# rwqs.net
KiCad netlist of a schematic drawn in EAGLE
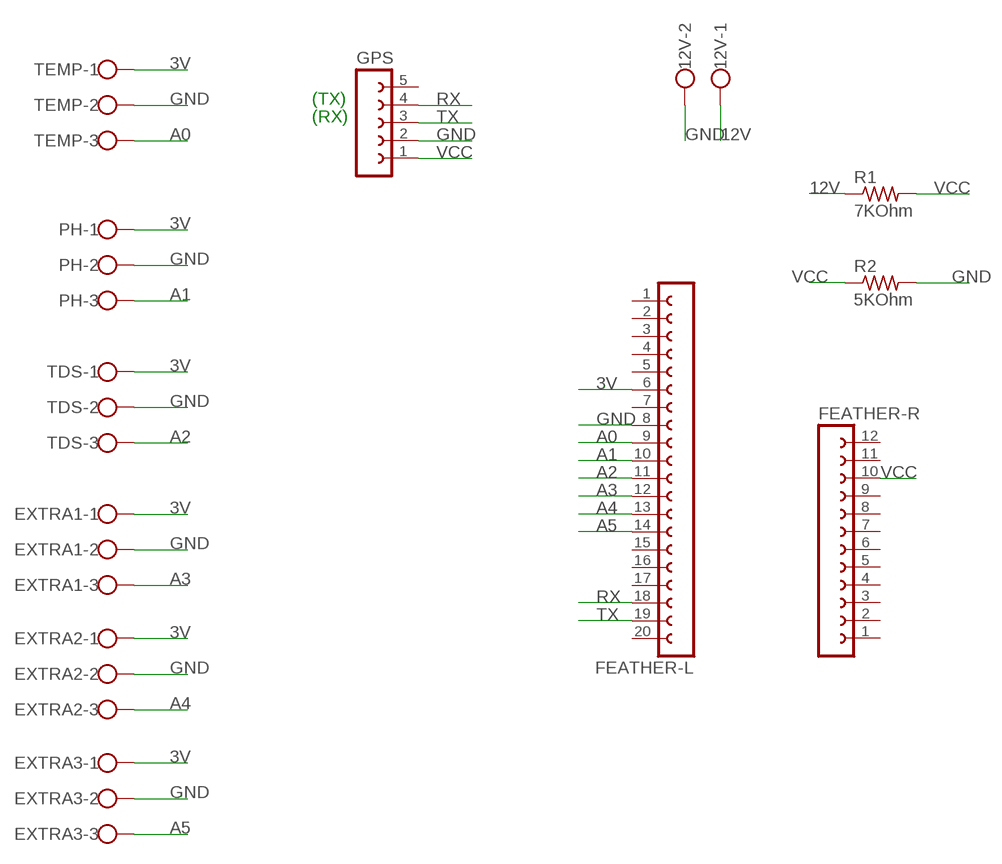
[diagram p0: schematic, sheet 1]

(export (version "E")
  (design (tool "Eeschema 10.0.6"))
  (components
    (comp (ref "12V")
      (value "W237-113")
      (footprint "eagle-import:W237-113")
      (libsource (lib "eagle-import") (part "W237-113"))
    )
    (comp (ref "EXTRA1")
      (value "W237-103")
      (footprint "eagle-import:W237-103")
      (fields (field (name "MPN") "237-103"))
      (libsource (lib "eagle-import") (part "W237-103"))
    )
    (comp (ref "EXTRA2")
      (value "W237-103")
      (footprint "eagle-import:W237-103")
      (fields (field (name "MPN") "237-103"))
      (libsource (lib "eagle-import") (part "W237-103"))
    )
    (comp (ref "EXTRA3")
      (value "W237-103")
      (footprint "eagle-import:W237-103")
      (fields (field (name "MPN") "237-103"))
      (libsource (lib "eagle-import") (part "W237-103"))
    )
    (comp (ref "FEATHER-L")
      (value "FE20-1")
      (footprint "eagle-import:FE20")
      (libsource (lib "eagle-import") (part "FE20-1"))
    )
    (comp (ref "FEATHER-R")
      (value "FE12-1")
      (footprint "eagle-import:FE12")
      (libsource (lib "eagle-import") (part "FE12-1"))
    )
    (comp (ref "GPS")
      (value "FE05-1")
      (footprint "eagle-import:FE05-1")
      (libsource (lib "eagle-import") (part "FE05-1"))
    )
    (comp (ref "PH")
      (value "W237-103")
      (footprint "eagle-import:W237-103")
      (fields (field (name "MPN") "237-103"))
      (libsource (lib "eagle-import") (part "W237-103"))
    )
    (comp (ref "R1")
      (value "7KOhm")
      (footprint "eagle-import:0204V")
      (libsource (lib "eagle-import") (part "R-US_0204/2V"))
    )
    (comp (ref "R2")
      (value "5KOhm")
      (footprint "eagle-import:0204V")
      (libsource (lib "eagle-import") (part "R-US_0204/2V"))
    )
    (comp (ref "TDS")
      (value "W237-103")
      (footprint "eagle-import:W237-103")
      (fields (field (name "MPN") "237-103"))
      (libsource (lib "eagle-import") (part "W237-103"))
    )
    (comp (ref "TEMP")
      (value "W237-103")
      (footprint "eagle-import:W237-103")
      (fields (field (name "MPN") "237-103"))
      (libsource (lib "eagle-import") (part "W237-103"))
    )
  )
  (nets
    (net (code "1") (name "/3V") (class "Default")
      (node (ref "EXTRA1") (pin "1") (pinfunction "KL_1") (pintype "passive"))
      (node (ref "EXTRA2") (pin "1") (pinfunction "KL_1") (pintype "passive"))
      (node (ref "EXTRA3") (pin "1") (pinfunction "KL_1") (pintype "passive"))
      (node (ref "FEATHER-L") (pin "6") (pinfunction "6_6") (pintype "passive"))
      (node (ref "PH") (pin "1") (pinfunction "KL_1") (pintype "passive"))
      (node (ref "TDS") (pin "1") (pinfunction "KL_1") (pintype "passive"))
      (node (ref "TEMP") (pin "1") (pinfunction "KL_1") (pintype "passive"))
    )
    (net (code "2") (name "/12V") (class "Default")
      (node (ref "12V") (pin "1") (pinfunction "KL_1") (pintype "passive"))
      (node (ref "R1") (pin "1") (pinfunction "1_1") (pintype "passive"))
    )
    (net (code "3") (name "/A0") (class "Default")
      (node (ref "FEATHER-L") (pin "9") (pinfunction "9_9") (pintype "passive"))
      (node (ref "TEMP") (pin "3") (pinfunction "KL_3") (pintype "passive"))
    )
    (net (code "4") (name "/A1") (class "Default")
      (node (ref "FEATHER-L") (pin "10") (pinfunction "10_10") (pintype "passive"))
      (node (ref "PH") (pin "3") (pinfunction "KL_3") (pintype "passive"))
    )
    (net (code "5") (name "/A2") (class "Default")
      (node (ref "FEATHER-L") (pin "11") (pinfunction "11_11") (pintype "passive"))
      (node (ref "TDS") (pin "3") (pinfunction "KL_3") (pintype "passive"))
    )
    (net (code "6") (name "/A3") (class "Default")
      (node (ref "EXTRA1") (pin "3") (pinfunction "KL_3") (pintype "passive"))
      (node (ref "FEATHER-L") (pin "12") (pinfunction "12_12") (pintype "passive"))
    )
    (net (code "7") (name "/A4") (class "Default")
      (node (ref "EXTRA2") (pin "3") (pinfunction "KL_3") (pintype "passive"))
      (node (ref "FEATHER-L") (pin "13") (pinfunction "13_13") (pintype "passive"))
    )
    (net (code "8") (name "/A5") (class "Default")
      (node (ref "EXTRA3") (pin "3") (pinfunction "KL_3") (pintype "passive"))
      (node (ref "FEATHER-L") (pin "14") (pinfunction "14_14") (pintype "passive"))
    )
    (net (code "9") (name "/GND") (class "Default")
      (node (ref "12V") (pin "2") (pinfunction "KL_2") (pintype "passive"))
      (node (ref "EXTRA1") (pin "2") (pinfunction "KL_2") (pintype "passive"))
      (node (ref "EXTRA2") (pin "2") (pinfunction "KL_2") (pintype "passive"))
      (node (ref "EXTRA3") (pin "2") (pinfunction "KL_2") (pintype "passive"))
      (node (ref "FEATHER-L") (pin "8") (pinfunction "8_8") (pintype "passive"))
      (node (ref "GPS") (pin "2") (pinfunction "2_2") (pintype "passive"))
      (node (ref "PH") (pin "2") (pinfunction "KL_2") (pintype "passive"))
      (node (ref "R2") (pin "2") (pinfunction "2_2") (pintype "passive"))
      (node (ref "TDS") (pin "2") (pinfunction "KL_2") (pintype "passive"))
      (node (ref "TEMP") (pin "2") (pinfunction "KL_2") (pintype "passive"))
    )
    (net (code "10") (name "/RX") (class "Default")
      (node (ref "FEATHER-L") (pin "18") (pinfunction "18_18") (pintype "passive"))
      (node (ref "GPS") (pin "4") (pinfunction "4_4") (pintype "passive"))
    )
    (net (code "11") (name "/TX") (class "Default")
      (node (ref "FEATHER-L") (pin "19") (pinfunction "19_19") (pintype "passive"))
      (node (ref "GPS") (pin "3") (pinfunction "3_3") (pintype "passive"))
    )
    (net (code "12") (name "/VCC") (class "Default")
      (node (ref "FEATHER-R") (pin "10") (pinfunction "10_10") (pintype "passive"))
      (node (ref "GPS") (pin "1") (pinfunction "1_1") (pintype "passive"))
      (node (ref "R1") (pin "2") (pinfunction "2_2") (pintype "passive"))
      (node (ref "R2") (pin "1") (pinfunction "1_1") (pintype "passive"))
    )
    (net (code "13") (name "unconnected-(FEATHER-L-Pad1)") (class "Default")
      (node (ref "FEATHER-L") (pin "1") (pinfunction "1_1") (pintype "passive"))
    )
    (net (code "14") (name "unconnected-(FEATHER-L-Pad2)") (class "Default")
      (node (ref "FEATHER-L") (pin "2") (pinfunction "2_2") (pintype "passive"))
    )
    (net (code "15") (name "unconnected-(FEATHER-L-Pad3)") (class "Default")
      (node (ref "FEATHER-L") (pin "3") (pinfunction "3_3") (pintype "passive"))
    )
    (net (code "16") (name "unconnected-(FEATHER-L-Pad4)") (class "Default")
      (node (ref "FEATHER-L") (pin "4") (pinfunction "4_4") (pintype "passive"))
    )
    (net (code "17") (name "unconnected-(FEATHER-L-Pad5)") (class "Default")
      (node (ref "FEATHER-L") (pin "5") (pinfunction "5_5") (pintype "passive"))
    )
    (net (code "18") (name "unconnected-(FEATHER-L-Pad7)") (class "Default")
      (node (ref "FEATHER-L") (pin "7") (pinfunction "7_7") (pintype "passive"))
    )
    (net (code "19") (name "unconnected-(FEATHER-L-Pad15)") (class "Default")
      (node (ref "FEATHER-L") (pin "15") (pinfunction "15_15") (pintype "passive"))
    )
    (net (code "20") (name "unconnected-(FEATHER-L-Pad16)") (class "Default")
      (node (ref "FEATHER-L") (pin "16") (pinfunction "16_16") (pintype "passive"))
    )
    (net (code "21") (name "unconnected-(FEATHER-L-Pad17)") (class "Default")
      (node (ref "FEATHER-L") (pin "17") (pinfunction "17_17") (pintype "passive"))
    )
    (net (code "22") (name "unconnected-(FEATHER-L-Pad20)") (class "Default")
      (node (ref "FEATHER-L") (pin "20") (pinfunction "20_20") (pintype "passive"))
    )
    (net (code "23") (name "unconnected-(FEATHER-R-Pad1)") (class "Default")
      (node (ref "FEATHER-R") (pin "1") (pinfunction "1_1") (pintype "passive"))
    )
    (net (code "24") (name "unconnected-(FEATHER-R-Pad2)") (class "Default")
      (node (ref "FEATHER-R") (pin "2") (pinfunction "2_2") (pintype "passive"))
    )
    (net (code "25") (name "unconnected-(FEATHER-R-Pad3)") (class "Default")
      (node (ref "FEATHER-R") (pin "3") (pinfunction "3_3") (pintype "passive"))
    )
    (net (code "26") (name "unconnected-(FEATHER-R-Pad4)") (class "Default")
      (node (ref "FEATHER-R") (pin "4") (pinfunction "4_4") (pintype "passive"))
    )
    (net (code "27") (name "unconnected-(FEATHER-R-Pad5)") (class "Default")
      (node (ref "FEATHER-R") (pin "5") (pinfunction "5_5") (pintype "passive"))
    )
    (net (code "28") (name "unconnected-(FEATHER-R-Pad6)") (class "Default")
      (node (ref "FEATHER-R") (pin "6") (pinfunction "6_6") (pintype "passive"))
    )
    (net (code "29") (name "unconnected-(FEATHER-R-Pad7)") (class "Default")
      (node (ref "FEATHER-R") (pin "7") (pinfunction "7_7") (pintype "passive"))
    )
    (net (code "30") (name "unconnected-(FEATHER-R-Pad8)") (class "Default")
      (node (ref "FEATHER-R") (pin "8") (pinfunction "8_8") (pintype "passive"))
    )
    (net (code "31") (name "unconnected-(FEATHER-R-Pad9)") (class "Default")
      (node (ref "FEATHER-R") (pin "9") (pinfunction "9_9") (pintype "passive"))
    )
    (net (code "32") (name "unconnected-(FEATHER-R-Pad11)") (class "Default")
      (node (ref "FEATHER-R") (pin "11") (pinfunction "11_11") (pintype "passive"))
    )
    (net (code "33") (name "unconnected-(FEATHER-R-Pad12)") (class "Default")
      (node (ref "FEATHER-R") (pin "12") (pinfunction "12_12") (pintype "passive"))
    )
    (net (code "34") (name "unconnected-(GPS-Pad5)") (class "Default")
      (node (ref "GPS") (pin "5") (pinfunction "5_5") (pintype "passive"))
    )
  )
)
